# ioboard.net
KiCad netlist of a schematic drawn in EAGLE
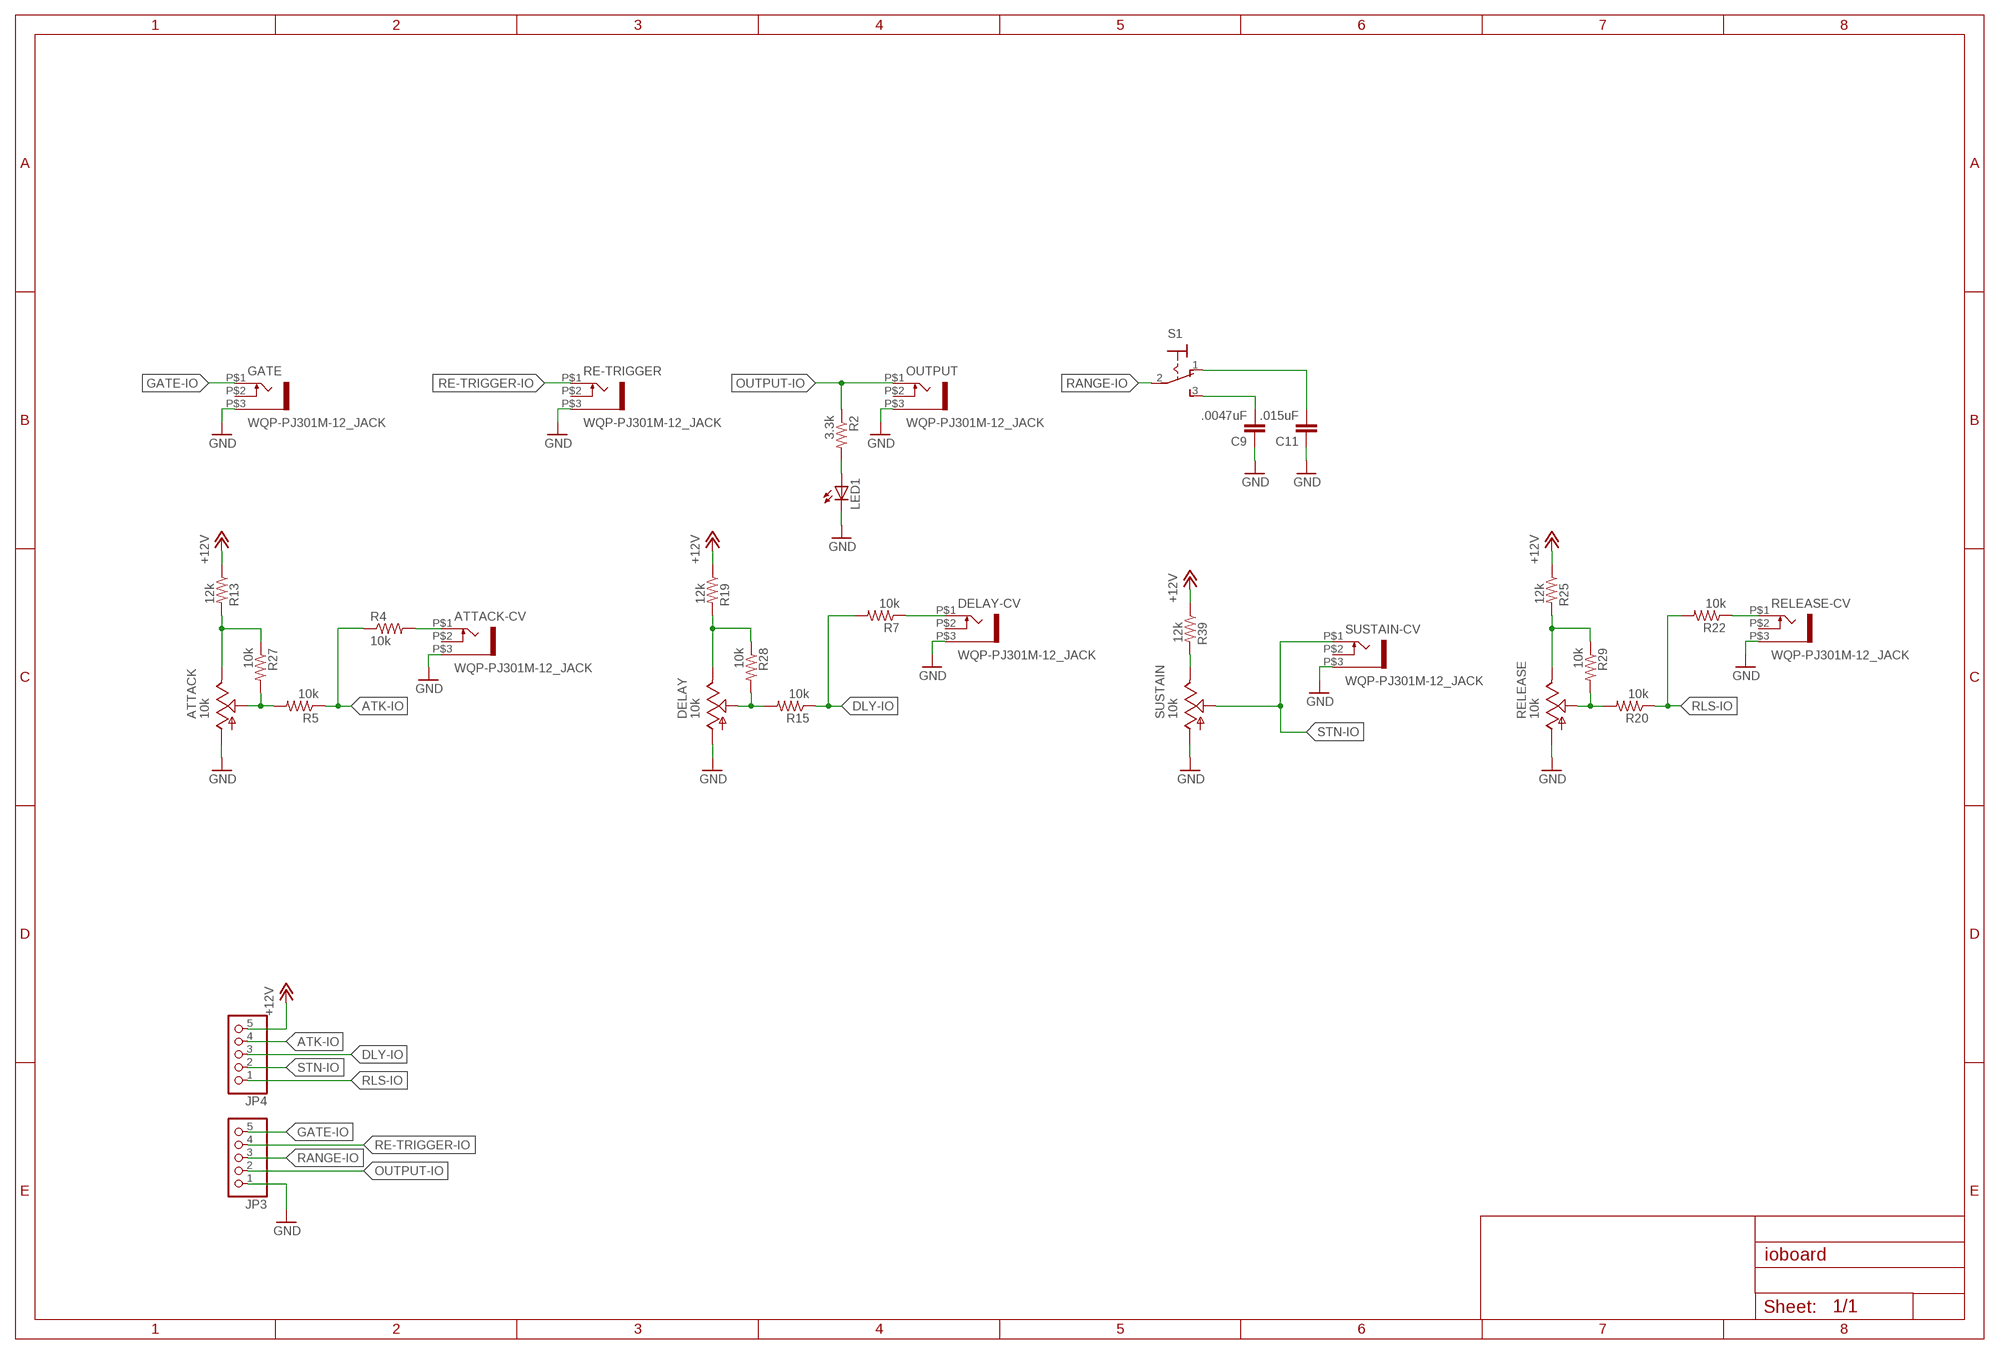
[diagram p0: schematic, sheet 1]

(export (version "E")
  (design (tool "Eeschema 10.0.6"))
  (components
    (comp (ref "ATTACK")
      (value "10k")
      (footprint "eagle-import:EVUF")
      (libsource (lib "eagle-import") (part "ALPHA-9MMA"))
    )
    (comp (ref "ATTACK-CV")
      (value "WQP-PJ301M-12_JACK")
      (footprint "eagle-import:WQP-PJ301M-12_JACK")
      (libsource (lib "eagle-import") (part "WQP-PJ301M-12_JACK"))
    )
    (comp (ref "C9")
      (value ".0047uF")
      (footprint "eagle-import:C050-024X044")
      (libsource (lib "eagle-import") (part "C-EU050-024X044"))
    )
    (comp (ref "C11")
      (value ".015uF")
      (footprint "eagle-import:C050-024X044")
      (libsource (lib "eagle-import") (part "C-EU050-024X044"))
    )
    (comp (ref "DELAY")
      (value "10k")
      (footprint "eagle-import:EVUF")
      (libsource (lib "eagle-import") (part "ALPHA-9MMA"))
    )
    (comp (ref "DELAY-CV")
      (value "WQP-PJ301M-12_JACK")
      (footprint "eagle-import:WQP-PJ301M-12_JACK")
      (libsource (lib "eagle-import") (part "WQP-PJ301M-12_JACK"))
    )
    (comp (ref "GATE")
      (value "WQP-PJ301M-12_JACK")
      (footprint "eagle-import:WQP-PJ301M-12_JACK")
      (libsource (lib "eagle-import") (part "WQP-PJ301M-12_JACK"))
    )
    (comp (ref "JP3")
      (value "PINHD-1X5")
      (footprint "eagle-import:1X05")
      (libsource (lib "eagle-import") (part "PINHD-1X5"))
    )
    (comp (ref "JP4")
      (value "PINHD-1X5")
      (footprint "eagle-import:1X05")
      (libsource (lib "eagle-import") (part "PINHD-1X5"))
    )
    (comp (ref "LED1")
      (value "LED5MM")
      (footprint "eagle-import:LED5MM")
      (libsource (lib "eagle-import") (part "LED5MM"))
    )
    (comp (ref "OUTPUT")
      (value "WQP-PJ301M-12_JACK")
      (footprint "eagle-import:WQP-PJ301M-12_JACK")
      (libsource (lib "eagle-import") (part "WQP-PJ301M-12_JACK"))
    )
    (comp (ref "R2")
      (value "3.3k")
      (footprint "eagle-import:0207_7")
      (libsource (lib "eagle-import") (part "R-US_0207/7"))
    )
    (comp (ref "R4")
      (value "10k")
      (footprint "eagle-import:0207_7")
      (libsource (lib "eagle-import") (part "R-US_0207/7"))
    )
    (comp (ref "R5")
      (value "10k")
      (footprint "eagle-import:0207_7")
      (libsource (lib "eagle-import") (part "R-US_0207/7"))
    )
    (comp (ref "R7")
      (value "10k")
      (footprint "eagle-import:0207_7")
      (libsource (lib "eagle-import") (part "R-US_0207/7"))
    )
    (comp (ref "R13")
      (value "12k")
      (footprint "eagle-import:0207_7")
      (libsource (lib "eagle-import") (part "R-US_0207/7"))
    )
    (comp (ref "R15")
      (value "10k")
      (footprint "eagle-import:0207_7")
      (libsource (lib "eagle-import") (part "R-US_0207/7"))
    )
    (comp (ref "R19")
      (value "12k")
      (footprint "eagle-import:0207_7")
      (libsource (lib "eagle-import") (part "R-US_0207/7"))
    )
    (comp (ref "R20")
      (value "10k")
      (footprint "eagle-import:0207_7")
      (libsource (lib "eagle-import") (part "R-US_0207/7"))
    )
    (comp (ref "R22")
      (value "10k")
      (footprint "eagle-import:0207_7")
      (libsource (lib "eagle-import") (part "R-US_0207/7"))
    )
    (comp (ref "R25")
      (value "12k")
      (footprint "eagle-import:0207_7")
      (libsource (lib "eagle-import") (part "R-US_0207/7"))
    )
    (comp (ref "R27")
      (value "10k")
      (footprint "eagle-import:0207_7")
      (libsource (lib "eagle-import") (part "R-US_0207/7"))
    )
    (comp (ref "R28")
      (value "10k")
      (footprint "eagle-import:0207_7")
      (libsource (lib "eagle-import") (part "R-US_0207/7"))
    )
    (comp (ref "R29")
      (value "10k")
      (footprint "eagle-import:0207_7")
      (libsource (lib "eagle-import") (part "R-US_0207/7"))
    )
    (comp (ref "R39")
      (value "12k")
      (footprint "eagle-import:0207_7")
      (libsource (lib "eagle-import") (part "R-US_0207/7"))
    )
    (comp (ref "RE-TRIGGER")
      (value "WQP-PJ301M-12_JACK")
      (footprint "eagle-import:WQP-PJ301M-12_JACK")
      (libsource (lib "eagle-import") (part "WQP-PJ301M-12_JACK"))
    )
    (comp (ref "RELEASE")
      (value "10k")
      (footprint "eagle-import:EVUF")
      (libsource (lib "eagle-import") (part "ALPHA-9MMA"))
    )
    (comp (ref "RELEASE-CV")
      (value "WQP-PJ301M-12_JACK")
      (footprint "eagle-import:WQP-PJ301M-12_JACK")
      (libsource (lib "eagle-import") (part "WQP-PJ301M-12_JACK"))
    )
    (comp (ref "S1")
      (value "M9040P")
      (footprint "eagle-import:M9040P")
      (libsource (lib "eagle-import") (part "M9040P"))
    )
    (comp (ref "SUSTAIN")
      (value "10k")
      (footprint "eagle-import:EVUF")
      (libsource (lib "eagle-import") (part "ALPHA-9MMA"))
    )
    (comp (ref "SUSTAIN-CV")
      (value "WQP-PJ301M-12_JACK")
      (footprint "eagle-import:WQP-PJ301M-12_JACK")
      (libsource (lib "eagle-import") (part "WQP-PJ301M-12_JACK"))
    )
  )
  (nets
    (net (code "1") (name "+12V") (class "Default")
      (node (ref "JP4") (pin "5") (pinfunction "5_5") (pintype "passive"))
      (node (ref "R13") (pin "1") (pinfunction "1_1") (pintype "passive"))
      (node (ref "R19") (pin "1") (pinfunction "1_1") (pintype "passive"))
      (node (ref "R25") (pin "1") (pinfunction "1_1") (pintype "passive"))
      (node (ref "R39") (pin "1") (pinfunction "1_1") (pintype "passive"))
    )
    (net (code "2") (name "ATK-IO") (class "Default")
      (node (ref "JP4") (pin "4") (pinfunction "4_4") (pintype "passive"))
      (node (ref "R4") (pin "1") (pinfunction "1_1") (pintype "passive"))
      (node (ref "R5") (pin "1") (pinfunction "1_1") (pintype "passive"))
    )
    (net (code "3") (name "DLY-IO") (class "Default")
      (node (ref "JP4") (pin "3") (pinfunction "3_3") (pintype "passive"))
      (node (ref "R15") (pin "1") (pinfunction "1_1") (pintype "passive"))
      (node (ref "R7") (pin "2") (pinfunction "2_2") (pintype "passive"))
    )
    (net (code "4") (name "GATE-IO") (class "Default")
      (node (ref "GATE") (pin "P$1") (pinfunction "2_P$1") (pintype "passive"))
      (node (ref "JP3") (pin "5") (pinfunction "5_5") (pintype "passive"))
    )
    (net (code "5") (name "GND") (class "Default")
      (node (ref "ATTACK") (pin "1") (pinfunction "A_1") (pintype "passive"))
      (node (ref "ATTACK-CV") (pin "P$3") (pinfunction "1_P$3") (pintype "passive"))
      (node (ref "C11") (pin "1") (pinfunction "1_1") (pintype "passive"))
      (node (ref "C9") (pin "1") (pinfunction "1_1") (pintype "passive"))
      (node (ref "DELAY") (pin "1") (pinfunction "A_1") (pintype "passive"))
      (node (ref "DELAY-CV") (pin "P$3") (pinfunction "1_P$3") (pintype "passive"))
      (node (ref "GATE") (pin "P$3") (pinfunction "1_P$3") (pintype "passive"))
      (node (ref "JP3") (pin "1") (pinfunction "1_1") (pintype "passive"))
      (node (ref "LED1") (pin "K") (pinfunction "C_K") (pintype "passive"))
      (node (ref "OUTPUT") (pin "P$3") (pinfunction "1_P$3") (pintype "passive"))
      (node (ref "RE-TRIGGER") (pin "P$3") (pinfunction "1_P$3") (pintype "passive"))
      (node (ref "RELEASE") (pin "1") (pinfunction "A_1") (pintype "passive"))
      (node (ref "RELEASE-CV") (pin "P$3") (pinfunction "1_P$3") (pintype "passive"))
      (node (ref "SUSTAIN") (pin "1") (pinfunction "A_1") (pintype "passive"))
      (node (ref "SUSTAIN-CV") (pin "P$3") (pinfunction "1_P$3") (pintype "passive"))
    )
    (net (code "6") (name "Net-(ATTACK-CV-2)") (class "Default")
      (node (ref "ATTACK-CV") (pin "P$1") (pinfunction "2_P$1") (pintype "passive"))
      (node (ref "R4") (pin "2") (pinfunction "2_2") (pintype "passive"))
    )
    (net (code "7") (name "Net-(ATTACK-E)") (class "Default")
      (node (ref "ATTACK") (pin "3") (pinfunction "E_3") (pintype "passive"))
      (node (ref "R13") (pin "2") (pinfunction "2_2") (pintype "passive"))
      (node (ref "R27") (pin "1") (pinfunction "1_1") (pintype "passive"))
    )
    (net (code "8") (name "Net-(ATTACK-S)") (class "Default")
      (node (ref "ATTACK") (pin "2") (pinfunction "S_2") (pintype "passive"))
      (node (ref "R27") (pin "2") (pinfunction "2_2") (pintype "passive"))
      (node (ref "R5") (pin "2") (pinfunction "2_2") (pintype "passive"))
    )
    (net (code "9") (name "Net-(DELAY-CV-2)") (class "Default")
      (node (ref "DELAY-CV") (pin "P$1") (pinfunction "2_P$1") (pintype "passive"))
      (node (ref "R7") (pin "1") (pinfunction "1_1") (pintype "passive"))
    )
    (net (code "10") (name "Net-(DELAY-E)") (class "Default")
      (node (ref "DELAY") (pin "3") (pinfunction "E_3") (pintype "passive"))
      (node (ref "R19") (pin "2") (pinfunction "2_2") (pintype "passive"))
      (node (ref "R28") (pin "1") (pinfunction "1_1") (pintype "passive"))
    )
    (net (code "11") (name "Net-(DELAY-S)") (class "Default")
      (node (ref "DELAY") (pin "2") (pinfunction "S_2") (pintype "passive"))
      (node (ref "R15") (pin "2") (pinfunction "2_2") (pintype "passive"))
      (node (ref "R28") (pin "2") (pinfunction "2_2") (pintype "passive"))
    )
    (net (code "12") (name "Net-(LED1-PadA)") (class "Default")
      (node (ref "LED1") (pin "A") (pinfunction "A_A") (pintype "passive"))
      (node (ref "R2") (pin "2") (pinfunction "2_2") (pintype "passive"))
    )
    (net (code "13") (name "Net-(RELEASE-CV-2)") (class "Default")
      (node (ref "R22") (pin "1") (pinfunction "1_1") (pintype "passive"))
      (node (ref "RELEASE-CV") (pin "P$1") (pinfunction "2_P$1") (pintype "passive"))
    )
    (net (code "14") (name "Net-(RELEASE-E)") (class "Default")
      (node (ref "R25") (pin "2") (pinfunction "2_2") (pintype "passive"))
      (node (ref "R29") (pin "1") (pinfunction "1_1") (pintype "passive"))
      (node (ref "RELEASE") (pin "3") (pinfunction "E_3") (pintype "passive"))
    )
    (net (code "15") (name "Net-(RELEASE-S)") (class "Default")
      (node (ref "R20") (pin "2") (pinfunction "2_2") (pintype "passive"))
      (node (ref "R29") (pin "2") (pinfunction "2_2") (pintype "passive"))
      (node (ref "RELEASE") (pin "2") (pinfunction "S_2") (pintype "passive"))
    )
    (net (code "16") (name "Net-(S1-O)") (class "Default")
      (node (ref "C11") (pin "2") (pinfunction "2_2") (pintype "passive"))
      (node (ref "S1") (pin "1") (pinfunction "O_1") (pintype "passive"))
    )
    (net (code "17") (name "Net-(S1-S)") (class "Default")
      (node (ref "C9") (pin "2") (pinfunction "2_2") (pintype "passive"))
      (node (ref "S1") (pin "3") (pinfunction "S_3") (pintype "passive"))
    )
    (net (code "18") (name "Net-(SUSTAIN-E)") (class "Default")
      (node (ref "R39") (pin "2") (pinfunction "2_2") (pintype "passive"))
      (node (ref "SUSTAIN") (pin "3") (pinfunction "E_3") (pintype "passive"))
    )
    (net (code "19") (name "OUTPUT-IO") (class "Default")
      (node (ref "JP3") (pin "2") (pinfunction "2_2") (pintype "passive"))
      (node (ref "OUTPUT") (pin "P$1") (pinfunction "2_P$1") (pintype "passive"))
      (node (ref "R2") (pin "1") (pinfunction "1_1") (pintype "passive"))
    )
    (net (code "20") (name "RANGE-IO") (class "Default")
      (node (ref "JP3") (pin "3") (pinfunction "3_3") (pintype "passive"))
      (node (ref "S1") (pin "2") (pinfunction "P_2") (pintype "passive"))
    )
    (net (code "21") (name "RE-TRIGGER-IO") (class "Default")
      (node (ref "JP3") (pin "4") (pinfunction "4_4") (pintype "passive"))
      (node (ref "RE-TRIGGER") (pin "P$1") (pinfunction "2_P$1") (pintype "passive"))
    )
    (net (code "22") (name "RLS-IO") (class "Default")
      (node (ref "JP4") (pin "1") (pinfunction "1_1") (pintype "passive"))
      (node (ref "R20") (pin "1") (pinfunction "1_1") (pintype "passive"))
      (node (ref "R22") (pin "2") (pinfunction "2_2") (pintype "passive"))
    )
    (net (code "23") (name "STN-IO") (class "Default")
      (node (ref "JP4") (pin "2") (pinfunction "2_2") (pintype "passive"))
      (node (ref "SUSTAIN") (pin "2") (pinfunction "S_2") (pintype "passive"))
      (node (ref "SUSTAIN-CV") (pin "P$1") (pinfunction "2_P$1") (pintype "passive"))
    )
    (net (code "24") (name "unconnected-(ATTACK-CV-3-PadP$2)") (class "Default")
      (node (ref "ATTACK-CV") (pin "P$2") (pinfunction "3_P$2") (pintype "passive"))
    )
    (net (code "25") (name "unconnected-(DELAY-CV-3-PadP$2)") (class "Default")
      (node (ref "DELAY-CV") (pin "P$2") (pinfunction "3_P$2") (pintype "passive"))
    )
    (net (code "26") (name "unconnected-(GATE-3-PadP$2)") (class "Default")
      (node (ref "GATE") (pin "P$2") (pinfunction "3_P$2") (pintype "passive"))
    )
    (net (code "27") (name "unconnected-(OUTPUT-3-PadP$2)") (class "Default")
      (node (ref "OUTPUT") (pin "P$2") (pinfunction "3_P$2") (pintype "passive"))
    )
    (net (code "28") (name "unconnected-(RE-TRIGGER-3-PadP$2)") (class "Default")
      (node (ref "RE-TRIGGER") (pin "P$2") (pinfunction "3_P$2") (pintype "passive"))
    )
    (net (code "29") (name "unconnected-(RELEASE-CV-3-PadP$2)") (class "Default")
      (node (ref "RELEASE-CV") (pin "P$2") (pinfunction "3_P$2") (pintype "passive"))
    )
    (net (code "30") (name "unconnected-(SUSTAIN-CV-3-PadP$2)") (class "Default")
      (node (ref "SUSTAIN-CV") (pin "P$2") (pinfunction "3_P$2") (pintype "passive"))
    )
  )
)
